# Sheet2.net
KiCad netlist of a schematic drawn in Altium Designer
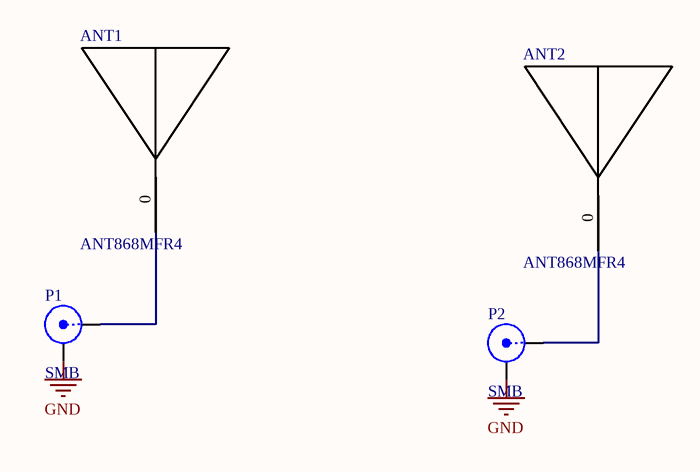
[diagram p0: Sheet2.SchDoc]

(export (version "E")
  (design (tool "Eeschema 10.0.6"))
  (components
    (comp (ref "ANT1")
      (value "ANT868MFR4")
      (footprint "ANT2G4FR4")
      (libsource (lib "AntLib") (part "ANT868MFR4"))
    )
    (comp (ref "ANT2")
      (value "ANT868MFR4")
      (footprint "ANT2G4FR4")
      (libsource (lib "AntLib") (part "ANT868MFR4"))
    )
    (comp (ref "P1")
      (value "SMB")
      (footprint "SMB_V-RJ45")
      (description "SMB Straight Connector")
      (fields (field (name "PUBLISHER") "Altium Limited"))
      (libsource (lib "Miscellaneous Connectors") (part "SMB"))
    )
    (comp (ref "P2")
      (value "SMB")
      (footprint "SMB_V-RJ45")
      (description "SMB Straight Connector")
      (fields (field (name "PUBLISHER") "Altium Limited"))
      (libsource (lib "Miscellaneous Connectors") (part "SMB"))
    )
  )
  (nets
    (net (code "1") (name "GND") (class "Default")
      (node (ref "P1") (pin "2") (pinfunction "Y_2") (pintype "passive"))
      (node (ref "P2") (pin "2") (pinfunction "Y_2") (pintype "passive"))
    )
    (net (code "2") (name "Net-(P1-X)") (class "Default")
      (node (ref "ANT1") (pin "0") (pinfunction "0_0") (pintype "passive"))
      (node (ref "P1") (pin "1") (pinfunction "X_1") (pintype "passive"))
    )
    (net (code "3") (name "Net-(P2-X)") (class "Default")
      (node (ref "ANT2") (pin "0") (pinfunction "0_0") (pintype "passive"))
      (node (ref "P2") (pin "1") (pinfunction "X_1") (pintype "passive"))
    )
  )
)
